# PicKit2Clone2.net
KiCad netlist of a schematic drawn in EAGLE
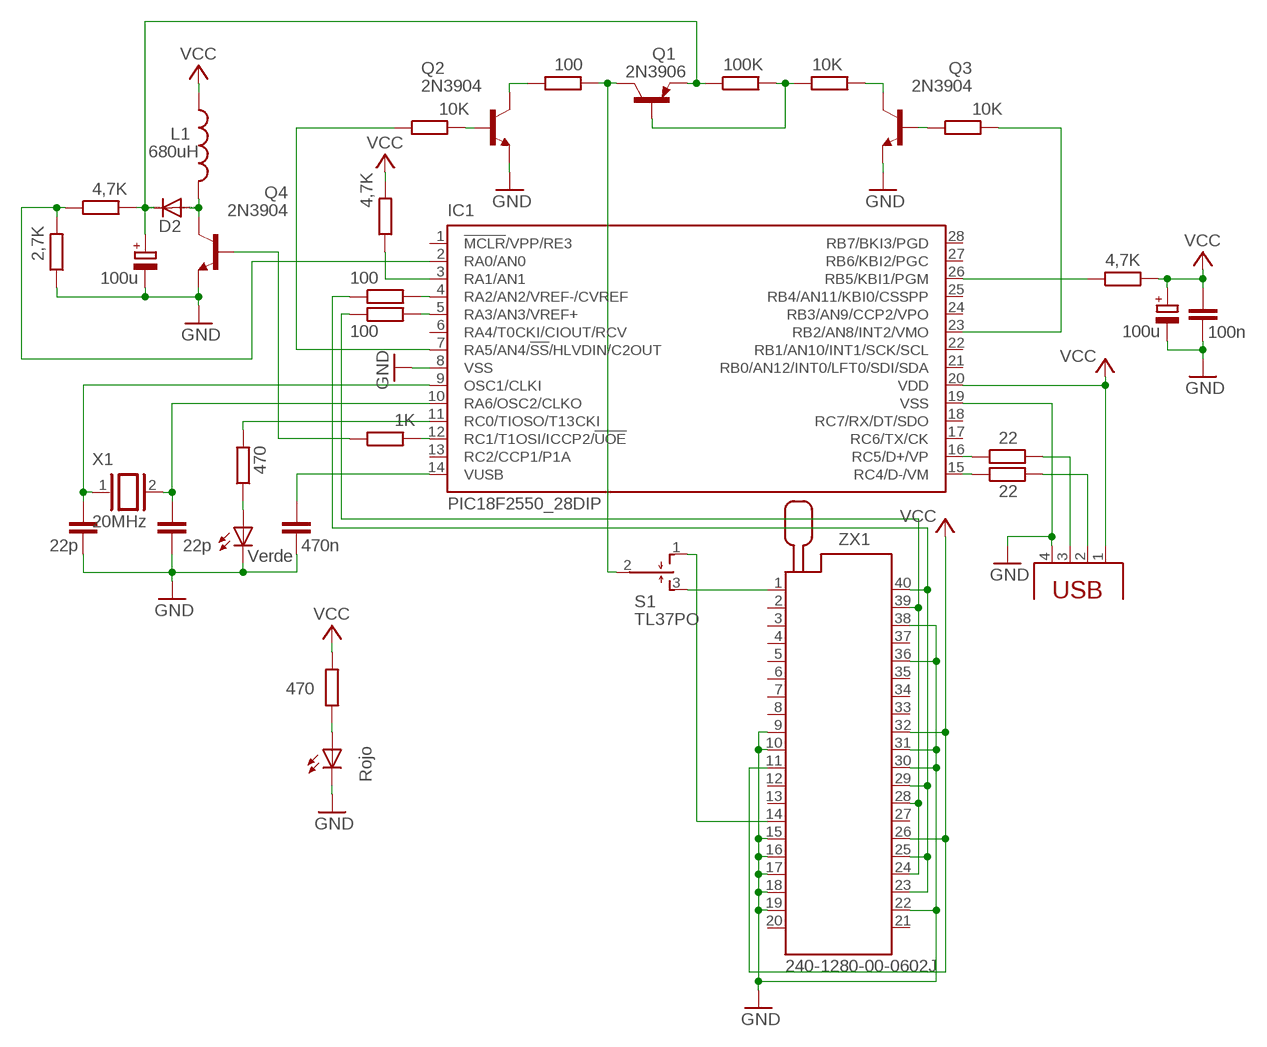
[diagram p0: schematic, sheet 1]

(export (version "E")
  (design (tool "Eeschema 10.0.6"))
  (components
    (comp (ref "C1")
      (value "22p")
      (footprint "eagle-import:C075-032X103")
      (libsource (lib "eagle-import") (part "C-EU075-032X103"))
    )
    (comp (ref "C2")
      (value "22p")
      (footprint "eagle-import:C075-032X103")
      (libsource (lib "eagle-import") (part "C-EU075-032X103"))
    )
    (comp (ref "C3")
      (value "100n")
      (footprint "eagle-import:C075-032X103")
      (libsource (lib "eagle-import") (part "C-EU075-032X103"))
    )
    (comp (ref "C4")
      (value "100u")
      (footprint "eagle-import:E2,5-6E")
      (libsource (lib "eagle-import") (part "CPOL-EUE2,5-6E"))
    )
    (comp (ref "C5")
      (value "470n")
      (footprint "eagle-import:C075-032X103")
      (libsource (lib "eagle-import") (part "C-EU075-032X103"))
    )
    (comp (ref "C6")
      (value "100u")
      (footprint "eagle-import:E2,5-6E")
      (libsource (lib "eagle-import") (part "CPOL-EUE2,5-6E"))
    )
    (comp (ref "D2")
      (value "1N4148DO35-7")
      (footprint "eagle-import:DO35-7")
      (libsource (lib "eagle-import") (part "1N4148DO35-7"))
    )
    (comp (ref "IC1")
      (value "PIC18F2550_28DIP")
      (footprint "eagle-import:DIL28-3")
      (fields (field (name "MF") "MICROCHIP") (field (name "MPN") "PIC18F2550-I/SP"))
      (libsource (lib "eagle-import") (part "PIC18F2_28DIP550"))
    )
    (comp (ref "L1")
      (value "680uH")
      (footprint "eagle-import:0207_7")
      (libsource (lib "eagle-import") (part "L-US0207/7"))
    )
    (comp (ref "LED1")
      (value "Verde")
      (footprint "eagle-import:LED3MM")
      (libsource (lib "eagle-import") (part "LED3MM"))
    )
    (comp (ref "LED2")
      (value "Rojo")
      (footprint "eagle-import:LED3MM")
      (libsource (lib "eagle-import") (part "LED3MM"))
    )
    (comp (ref "Q1")
      (value "2N3906")
      (footprint "eagle-import:TO92")
      (libsource (lib "eagle-import") (part "2N3906"))
    )
    (comp (ref "Q2")
      (value "2N3904")
      (footprint "eagle-import:TO92")
      (libsource (lib "eagle-import") (part "2N3904"))
    )
    (comp (ref "Q3")
      (value "2N3904")
      (footprint "eagle-import:TO92")
      (libsource (lib "eagle-import") (part "2N3904"))
    )
    (comp (ref "Q4")
      (value "2N3904")
      (footprint "eagle-import:TO92")
      (libsource (lib "eagle-import") (part "2N3904"))
    )
    (comp (ref "R1")
      (value "22")
      (footprint "eagle-import:0207_7")
      (libsource (lib "eagle-import") (part "R-EU_0207/7"))
    )
    (comp (ref "R2")
      (value "22")
      (footprint "eagle-import:0207_7")
      (libsource (lib "eagle-import") (part "R-EU_0207/7"))
    )
    (comp (ref "R3")
      (value "470")
      (footprint "eagle-import:0207_7")
      (libsource (lib "eagle-import") (part "R-EU_0207/7"))
    )
    (comp (ref "R4")
      (value "470")
      (footprint "eagle-import:0207_7")
      (libsource (lib "eagle-import") (part "R-EU_0207/7"))
    )
    (comp (ref "R5")
      (value "1K")
      (footprint "eagle-import:0207_7")
      (libsource (lib "eagle-import") (part "R-EU_0207/7"))
    )
    (comp (ref "R6")
      (value "2,7K")
      (footprint "eagle-import:0207_7")
      (libsource (lib "eagle-import") (part "R-EU_0207/7"))
    )
    (comp (ref "R7")
      (value "4,7K")
      (footprint "eagle-import:0207_7")
      (libsource (lib "eagle-import") (part "R-EU_0207/7"))
    )
    (comp (ref "R8")
      (value "100K")
      (footprint "eagle-import:0207_7")
      (libsource (lib "eagle-import") (part "R-EU_0207/7"))
    )
    (comp (ref "R9")
      (value "10K")
      (footprint "eagle-import:0207_7")
      (libsource (lib "eagle-import") (part "R-EU_0207/7"))
    )
    (comp (ref "R10")
      (value "10K")
      (footprint "eagle-import:0207_7")
      (libsource (lib "eagle-import") (part "R-EU_0207/7"))
    )
    (comp (ref "R11")
      (value "100")
      (footprint "eagle-import:0207_7")
      (libsource (lib "eagle-import") (part "R-EU_0207/7"))
    )
    (comp (ref "R12")
      (value "100")
      (footprint "eagle-import:0207_7")
      (libsource (lib "eagle-import") (part "R-EU_0207/7"))
    )
    (comp (ref "R13")
      (value "100")
      (footprint "eagle-import:0207_7")
      (libsource (lib "eagle-import") (part "R-EU_0207/7"))
    )
    (comp (ref "R14")
      (value "10K")
      (footprint "eagle-import:0207_7")
      (libsource (lib "eagle-import") (part "R-EU_0207/7"))
    )
    (comp (ref "R15")
      (value "4,7K")
      (footprint "eagle-import:0207_7")
      (libsource (lib "eagle-import") (part "R-EU_0207/7"))
    )
    (comp (ref "R16")
      (value "4,7K")
      (footprint "eagle-import:0207_7")
      (libsource (lib "eagle-import") (part "R-EU_0207/7"))
    )
    (comp (ref "S1")
      (value "TL37PO")
      (footprint "eagle-import:TL3XPO")
      (libsource (lib "eagle-import") (part "TL37PO"))
    )
    (comp (ref "USB")
      (value "PN87520")
      (footprint "eagle-import:PN87520")
      (libsource (lib "eagle-import") (part "PN87520"))
    )
    (comp (ref "X1")
      (value "20MHz")
      (footprint "eagle-import:QS")
      (libsource (lib "eagle-import") (part "XTAL/S"))
    )
    (comp (ref "ZX1")
      (value "240-1280-00-0602J")
      (footprint "eagle-import:240-1280-00-0602J")
      (fields (field (name "MF") "3M"))
      (libsource (lib "eagle-import") (part "240-?-00-0602J1280"))
    )
  )
  (nets
    (net (code "1") (name "GND") (class "Default")
      (node (ref "C1") (pin "2") (pinfunction "2_2") (pintype "passive"))
      (node (ref "C2") (pin "2") (pinfunction "2_2") (pintype "passive"))
      (node (ref "C3") (pin "1") (pinfunction "1_1") (pintype "passive"))
      (node (ref "C4") (pin "-") (pinfunction "-_-") (pintype "passive"))
      (node (ref "C5") (pin "1") (pinfunction "1_1") (pintype "passive"))
      (node (ref "C6") (pin "-") (pinfunction "-_-") (pintype "passive"))
      (node (ref "IC1") (pin "19") (pinfunction "VSS_19") (pintype "power_in"))
      (node (ref "IC1") (pin "8") (pinfunction "VSS_8") (pintype "power_in"))
      (node (ref "LED1") (pin "K") (pinfunction "C_K") (pintype "passive"))
      (node (ref "LED2") (pin "K") (pinfunction "C_K") (pintype "passive"))
      (node (ref "Q2") (pin "3") (pinfunction "E_3") (pintype "passive"))
      (node (ref "Q3") (pin "3") (pinfunction "E_3") (pintype "passive"))
      (node (ref "Q4") (pin "3") (pinfunction "E_3") (pintype "passive"))
      (node (ref "R6") (pin "1") (pinfunction "1_1") (pintype "passive"))
      (node (ref "USB") (pin "4") (pinfunction "4_4") (pintype "passive"))
      (node (ref "ZX1") (pin "10") (pinfunction "10_10") (pintype "passive"))
      (node (ref "ZX1") (pin "15") (pinfunction "15_15") (pintype "passive"))
      (node (ref "ZX1") (pin "16") (pinfunction "16_16") (pintype "passive"))
      (node (ref "ZX1") (pin "17") (pinfunction "17_17") (pintype "passive"))
      (node (ref "ZX1") (pin "18") (pinfunction "18_18") (pintype "passive"))
      (node (ref "ZX1") (pin "19") (pinfunction "19_19") (pintype "passive"))
      (node (ref "ZX1") (pin "22") (pinfunction "22_22") (pintype "passive"))
      (node (ref "ZX1") (pin "30") (pinfunction "30_30") (pintype "passive"))
      (node (ref "ZX1") (pin "31") (pinfunction "31_31") (pintype "passive"))
      (node (ref "ZX1") (pin "36") (pinfunction "36_36") (pintype "passive"))
      (node (ref "ZX1") (pin "38") (pinfunction "38_38") (pintype "passive"))
      (node (ref "ZX1") (pin "9") (pinfunction "9_9") (pintype "passive"))
    )
    (net (code "2") (name "Net-(IC1-OSC1{slash}CLKI)") (class "Default")
      (node (ref "C1") (pin "1") (pinfunction "1_1") (pintype "passive"))
      (node (ref "IC1") (pin "9") (pinfunction "OSC1/CLKI_9") (pintype "input"))
      (node (ref "X1") (pin "1") (pinfunction "1_1") (pintype "passive"))
    )
    (net (code "3") (name "Net-(IC1-RA0{slash}AN0)") (class "Default")
      (node (ref "IC1") (pin "2") (pinfunction "RA0/AN0_2") (pintype "bidirectional"))
      (node (ref "R16") (pin "1") (pinfunction "1_1") (pintype "passive"))
      (node (ref "R6") (pin "2") (pinfunction "2_2") (pintype "passive"))
    )
    (net (code "4") (name "Net-(IC1-RA1{slash}AN1)") (class "Default")
      (node (ref "IC1") (pin "3") (pinfunction "RA1/AN1_3") (pintype "bidirectional"))
      (node (ref "R15") (pin "1") (pinfunction "1_1") (pintype "passive"))
    )
    (net (code "5") (name "Net-(IC1-RA2{slash}AN2{slash}VREF-{slash}CVREF)") (class "Default")
      (node (ref "IC1") (pin "4") (pinfunction "RA2/AN2/VREF-/CVREF_4") (pintype "bidirectional"))
      (node (ref "R13") (pin "2") (pinfunction "2_2") (pintype "passive"))
    )
    (net (code "6") (name "Net-(IC1-RA3{slash}AN3{slash}VREF+)") (class "Default")
      (node (ref "IC1") (pin "5") (pinfunction "RA3/AN3/VREF+_5") (pintype "bidirectional"))
      (node (ref "R12") (pin "2") (pinfunction "2_2") (pintype "passive"))
    )
    (net (code "7") (name "Net-(IC1-RA5{slash}AN4{slash}~{SS}{slash}HLVDIN{slash}C2OUT)") (class "Default")
      (node (ref "IC1") (pin "7") (pinfunction "RA5/AN4/~{SS}/HLVDIN/C2OUT_7") (pintype "bidirectional"))
      (node (ref "R14") (pin "1") (pinfunction "1_1") (pintype "passive"))
    )
    (net (code "8") (name "Net-(IC1-RA6{slash}OSC2{slash}CLKO)") (class "Default")
      (node (ref "C2") (pin "1") (pinfunction "1_1") (pintype "passive"))
      (node (ref "IC1") (pin "10") (pinfunction "RA6/OSC2/CLKO_10") (pintype "output"))
      (node (ref "X1") (pin "2") (pinfunction "2_2") (pintype "passive"))
    )
    (net (code "9") (name "Net-(IC1-RB2{slash}AN8{slash}INT2{slash}VMO)") (class "Default")
      (node (ref "IC1") (pin "23") (pinfunction "RB2/AN8/INT2/VMO_23") (pintype "bidirectional"))
      (node (ref "R9") (pin "2") (pinfunction "2_2") (pintype "passive"))
    )
    (net (code "10") (name "Net-(IC1-RB5{slash}KBI1{slash}PGM)") (class "Default")
      (node (ref "IC1") (pin "26") (pinfunction "RB5/KBI1/PGM_26") (pintype "bidirectional"))
      (node (ref "R7") (pin "1") (pinfunction "1_1") (pintype "passive"))
    )
    (net (code "11") (name "Net-(IC1-RC0{slash}TIOSO{slash}T13CKI)") (class "Default")
      (node (ref "IC1") (pin "11") (pinfunction "RC0/TIOSO/T13CKI_11") (pintype "bidirectional"))
      (node (ref "R3") (pin "2") (pinfunction "2_2") (pintype "passive"))
    )
    (net (code "12") (name "Net-(IC1-RC1{slash}T1OSI{slash}ICCP2{slash}~{UOE})") (class "Default")
      (node (ref "IC1") (pin "12") (pinfunction "RC1/T1OSI/ICCP2/~{UOE}_12") (pintype "bidirectional"))
      (node (ref "R5") (pin "2") (pinfunction "2_2") (pintype "passive"))
    )
    (net (code "13") (name "Net-(IC1-RC4{slash}D-{slash}VM)") (class "Default")
      (node (ref "IC1") (pin "15") (pinfunction "RC4/D-/VM_15") (pintype "bidirectional"))
      (node (ref "R1") (pin "1") (pinfunction "1_1") (pintype "passive"))
    )
    (net (code "14") (name "Net-(IC1-RC5{slash}D+{slash}VP)") (class "Default")
      (node (ref "IC1") (pin "16") (pinfunction "RC5/D+/VP_16") (pintype "bidirectional"))
      (node (ref "R2") (pin "1") (pinfunction "1_1") (pintype "passive"))
    )
    (net (code "15") (name "Net-(IC1-VUSB)") (class "Default")
      (node (ref "C5") (pin "2") (pinfunction "2_2") (pintype "passive"))
      (node (ref "IC1") (pin "14") (pinfunction "VUSB_14") (pintype "bidirectional"))
    )
    (net (code "16") (name "Net-(LED1-PadA)") (class "Default")
      (node (ref "LED1") (pin "A") (pinfunction "A_A") (pintype "passive"))
      (node (ref "R3") (pin "1") (pinfunction "1_1") (pintype "passive"))
    )
    (net (code "17") (name "Net-(LED2-PadA)") (class "Default")
      (node (ref "LED2") (pin "A") (pinfunction "A_A") (pintype "passive"))
      (node (ref "R4") (pin "1") (pinfunction "1_1") (pintype "passive"))
    )
    (net (code "18") (name "Net-(Q1-B)") (class "Default")
      (node (ref "Q1") (pin "2") (pinfunction "B_2") (pintype "passive"))
      (node (ref "R10") (pin "1") (pinfunction "1_1") (pintype "passive"))
      (node (ref "R8") (pin "2") (pinfunction "2_2") (pintype "passive"))
    )
    (net (code "19") (name "Net-(Q1-C)") (class "Default")
      (node (ref "Q1") (pin "1") (pinfunction "C_1") (pintype "passive"))
      (node (ref "R11") (pin "2") (pinfunction "2_2") (pintype "passive"))
      (node (ref "S1") (pin "2") (pinfunction "P_2") (pintype "passive"))
    )
    (net (code "20") (name "Net-(Q1-E)") (class "Default")
      (node (ref "C6") (pin "+") (pinfunction "+_+") (pintype "passive"))
      (node (ref "D2") (pin "C") (pinfunction "C_C") (pintype "passive"))
      (node (ref "Q1") (pin "3") (pinfunction "E_3") (pintype "passive"))
      (node (ref "R16") (pin "2") (pinfunction "2_2") (pintype "passive"))
      (node (ref "R8") (pin "1") (pinfunction "1_1") (pintype "passive"))
    )
    (net (code "21") (name "Net-(Q2-B)") (class "Default")
      (node (ref "Q2") (pin "2") (pinfunction "B_2") (pintype "passive"))
      (node (ref "R14") (pin "2") (pinfunction "2_2") (pintype "passive"))
    )
    (net (code "22") (name "Net-(Q2-C)") (class "Default")
      (node (ref "Q2") (pin "1") (pinfunction "C_1") (pintype "passive"))
      (node (ref "R11") (pin "1") (pinfunction "1_1") (pintype "passive"))
    )
    (net (code "23") (name "Net-(Q3-B)") (class "Default")
      (node (ref "Q3") (pin "2") (pinfunction "B_2") (pintype "passive"))
      (node (ref "R9") (pin "1") (pinfunction "1_1") (pintype "passive"))
    )
    (net (code "24") (name "Net-(Q3-C)") (class "Default")
      (node (ref "Q3") (pin "1") (pinfunction "C_1") (pintype "passive"))
      (node (ref "R10") (pin "2") (pinfunction "2_2") (pintype "passive"))
    )
    (net (code "25") (name "Net-(Q4-B)") (class "Default")
      (node (ref "Q4") (pin "2") (pinfunction "B_2") (pintype "passive"))
      (node (ref "R5") (pin "1") (pinfunction "1_1") (pintype "passive"))
    )
    (net (code "26") (name "Net-(Q4-C)") (class "Default")
      (node (ref "D2") (pin "A") (pinfunction "A_A") (pintype "passive"))
      (node (ref "L1") (pin "2") (pinfunction "2_2") (pintype "passive"))
      (node (ref "Q4") (pin "1") (pinfunction "C_1") (pintype "passive"))
    )
    (net (code "27") (name "Net-(R1-Pad2)") (class "Default")
      (node (ref "R1") (pin "2") (pinfunction "2_2") (pintype "passive"))
      (node (ref "USB") (pin "2") (pinfunction "2_2") (pintype "passive"))
    )
    (net (code "28") (name "Net-(R2-Pad2)") (class "Default")
      (node (ref "R2") (pin "2") (pinfunction "2_2") (pintype "passive"))
      (node (ref "USB") (pin "3") (pinfunction "3_3") (pintype "passive"))
    )
    (net (code "29") (name "Net-(R12-Pad1)") (class "Default")
      (node (ref "R12") (pin "1") (pinfunction "1_1") (pintype "passive"))
      (node (ref "ZX1") (pin "24") (pinfunction "24_24") (pintype "passive"))
      (node (ref "ZX1") (pin "28") (pinfunction "28_28") (pintype "passive"))
      (node (ref "ZX1") (pin "39") (pinfunction "39_39") (pintype "passive"))
    )
    (net (code "30") (name "Net-(R13-Pad1)") (class "Default")
      (node (ref "R13") (pin "1") (pinfunction "1_1") (pintype "passive"))
      (node (ref "ZX1") (pin "23") (pinfunction "23_23") (pintype "passive"))
      (node (ref "ZX1") (pin "25") (pinfunction "25_25") (pintype "passive"))
      (node (ref "ZX1") (pin "29") (pinfunction "29_29") (pintype "passive"))
      (node (ref "ZX1") (pin "40") (pinfunction "40_40") (pintype "passive"))
    )
    (net (code "31") (name "Net-(S1-O)") (class "Default")
      (node (ref "S1") (pin "1") (pinfunction "O_1") (pintype "passive"))
      (node (ref "ZX1") (pin "14") (pinfunction "14_14") (pintype "passive"))
    )
    (net (code "32") (name "Net-(S1-S)") (class "Default")
      (node (ref "S1") (pin "3") (pinfunction "S_3") (pintype "passive"))
      (node (ref "ZX1") (pin "1") (pinfunction "1_1") (pintype "passive"))
    )
    (net (code "33") (name "VCC") (class "Default")
      (node (ref "C3") (pin "2") (pinfunction "2_2") (pintype "passive"))
      (node (ref "C4") (pin "+") (pinfunction "+_+") (pintype "passive"))
      (node (ref "IC1") (pin "20") (pinfunction "VDD_20") (pintype "power_in"))
      (node (ref "L1") (pin "1") (pinfunction "1_1") (pintype "passive"))
      (node (ref "R15") (pin "2") (pinfunction "2_2") (pintype "passive"))
      (node (ref "R4") (pin "2") (pinfunction "2_2") (pintype "passive"))
      (node (ref "R7") (pin "2") (pinfunction "2_2") (pintype "passive"))
      (node (ref "USB") (pin "1") (pinfunction "1_1") (pintype "passive"))
      (node (ref "ZX1") (pin "11") (pinfunction "11_11") (pintype "passive"))
      (node (ref "ZX1") (pin "26") (pinfunction "26_26") (pintype "passive"))
      (node (ref "ZX1") (pin "32") (pinfunction "32_32") (pintype "passive"))
    )
    (net (code "34") (name "unconnected-(IC1-RA4{slash}T0CKI{slash}CIOUT{slash}RCV-Pad6)") (class "Default")
      (node (ref "IC1") (pin "6") (pinfunction "RA4/T0CKI/CIOUT/RCV_6") (pintype "bidirectional"))
    )
    (net (code "35") (name "unconnected-(IC1-RB0{slash}AN12{slash}INT0{slash}LFT0{slash}SDI{slash}SDA-Pad21)") (class "Default")
      (node (ref "IC1") (pin "21") (pinfunction "RB0/AN12/INT0/LFT0/SDI/SDA_21") (pintype "bidirectional"))
    )
    (net (code "36") (name "unconnected-(IC1-RB1{slash}AN10{slash}INT1{slash}SCK{slash}SCL-Pad22)") (class "Default")
      (node (ref "IC1") (pin "22") (pinfunction "RB1/AN10/INT1/SCK/SCL_22") (pintype "bidirectional"))
    )
    (net (code "37") (name "unconnected-(IC1-RB3{slash}AN9{slash}CCP2{slash}VPO-Pad24)") (class "Default")
      (node (ref "IC1") (pin "24") (pinfunction "RB3/AN9/CCP2/VPO_24") (pintype "bidirectional"))
    )
    (net (code "38") (name "unconnected-(IC1-RB4{slash}AN11{slash}KBI0{slash}CSSPP-Pad25)") (class "Default")
      (node (ref "IC1") (pin "25") (pinfunction "RB4/AN11/KBI0/CSSPP_25") (pintype "bidirectional"))
    )
    (net (code "39") (name "unconnected-(IC1-RB6{slash}KBI2{slash}PGC-Pad27)") (class "Default")
      (node (ref "IC1") (pin "27") (pinfunction "RB6/KBI2/PGC_27") (pintype "bidirectional"))
    )
    (net (code "40") (name "unconnected-(IC1-RB7{slash}BKI3{slash}PGD-Pad28)") (class "Default")
      (node (ref "IC1") (pin "28") (pinfunction "RB7/BKI3/PGD_28") (pintype "bidirectional"))
    )
    (net (code "41") (name "unconnected-(IC1-RC2{slash}CCP1{slash}P1A-Pad13)") (class "Default")
      (node (ref "IC1") (pin "13") (pinfunction "RC2/CCP1/P1A_13") (pintype "bidirectional"))
    )
    (net (code "42") (name "unconnected-(IC1-RC6{slash}TX{slash}CK-Pad17)") (class "Default")
      (node (ref "IC1") (pin "17") (pinfunction "RC6/TX/CK_17") (pintype "bidirectional"))
    )
    (net (code "43") (name "unconnected-(IC1-RC7{slash}RX{slash}DT{slash}SDO-Pad18)") (class "Default")
      (node (ref "IC1") (pin "18") (pinfunction "RC7/RX/DT/SDO_18") (pintype "bidirectional"))
    )
    (net (code "44") (name "unconnected-(IC1-~{MCLR}{slash}VPP{slash}RE3-Pad1)") (class "Default")
      (node (ref "IC1") (pin "1") (pinfunction "~{MCLR}/VPP/RE3_1") (pintype "input"))
    )
    (net (code "45") (name "unconnected-(ZX1-Pad2)") (class "Default")
      (node (ref "ZX1") (pin "2") (pinfunction "2_2") (pintype "passive"))
    )
    (net (code "46") (name "unconnected-(ZX1-Pad3)") (class "Default")
      (node (ref "ZX1") (pin "3") (pinfunction "3_3") (pintype "passive"))
    )
    (net (code "47") (name "unconnected-(ZX1-Pad4)") (class "Default")
      (node (ref "ZX1") (pin "4") (pinfunction "4_4") (pintype "passive"))
    )
    (net (code "48") (name "unconnected-(ZX1-Pad5)") (class "Default")
      (node (ref "ZX1") (pin "5") (pinfunction "5_5") (pintype "passive"))
    )
    (net (code "49") (name "unconnected-(ZX1-Pad6)") (class "Default")
      (node (ref "ZX1") (pin "6") (pinfunction "6_6") (pintype "passive"))
    )
    (net (code "50") (name "unconnected-(ZX1-Pad7)") (class "Default")
      (node (ref "ZX1") (pin "7") (pinfunction "7_7") (pintype "passive"))
    )
    (net (code "51") (name "unconnected-(ZX1-Pad8)") (class "Default")
      (node (ref "ZX1") (pin "8") (pinfunction "8_8") (pintype "passive"))
    )
    (net (code "52") (name "unconnected-(ZX1-Pad12)") (class "Default")
      (node (ref "ZX1") (pin "12") (pinfunction "12_12") (pintype "passive"))
    )
    (net (code "53") (name "unconnected-(ZX1-Pad13)") (class "Default")
      (node (ref "ZX1") (pin "13") (pinfunction "13_13") (pintype "passive"))
    )
    (net (code "54") (name "unconnected-(ZX1-Pad20)") (class "Default")
      (node (ref "ZX1") (pin "20") (pinfunction "20_20") (pintype "passive"))
    )
    (net (code "55") (name "unconnected-(ZX1-Pad21)") (class "Default")
      (node (ref "ZX1") (pin "21") (pinfunction "21_21") (pintype "passive"))
    )
    (net (code "56") (name "unconnected-(ZX1-Pad27)") (class "Default")
      (node (ref "ZX1") (pin "27") (pinfunction "27_27") (pintype "passive"))
    )
    (net (code "57") (name "unconnected-(ZX1-Pad33)") (class "Default")
      (node (ref "ZX1") (pin "33") (pinfunction "33_33") (pintype "passive"))
    )
    (net (code "58") (name "unconnected-(ZX1-Pad34)") (class "Default")
      (node (ref "ZX1") (pin "34") (pinfunction "34_34") (pintype "passive"))
    )
    (net (code "59") (name "unconnected-(ZX1-Pad35)") (class "Default")
      (node (ref "ZX1") (pin "35") (pinfunction "35_35") (pintype "passive"))
    )
    (net (code "60") (name "unconnected-(ZX1-Pad37)") (class "Default")
      (node (ref "ZX1") (pin "37") (pinfunction "37_37") (pintype "passive"))
    )
  )
)
